# lmr33620.net
KiCad netlist of a schematic drawn in Altium Designer
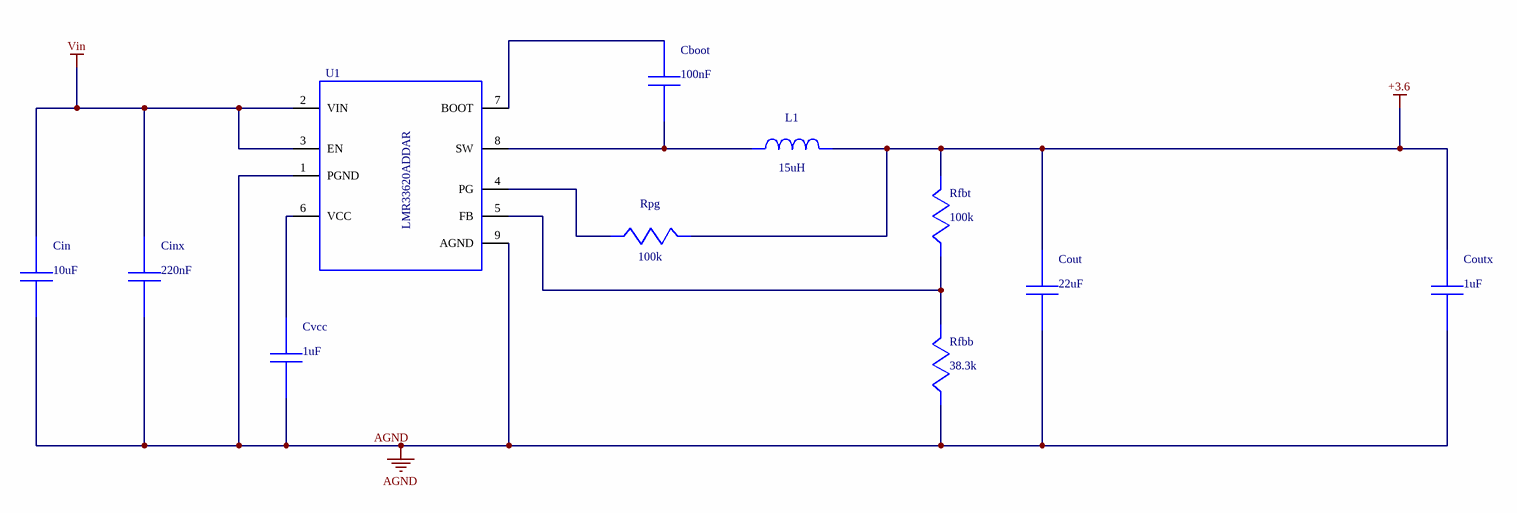
[diagram p0: lmr33620.schdoc]

(export (version "E")
  (design (tool "Eeschema 10.0.6"))
  (components
    (comp (ref "Cboot")
      (value "100nF")
      (footprint "0805_C")
      (description "HMK212B7104KG-T")
      (libsource (lib "TI WEBENCH") (part "Cboot"))
    )
    (comp (ref "Cin")
      (value "10uF")
      (footprint "1206_C")
      (description "C3216X5R1H106K16")
      (fields (field (name "BOM_MANUFACTURER PART") "C3216X5R1H106K160AB"))
      (libsource (lib "TI WEBENCH") (part "Cin"))
    )
    (comp (ref "Cinx")
      (value "220nF")
      (footprint "1206_C")
      (description "C3216X7R2A224K11")
      (fields (field (name "BOM_MANUFACTURER PART") "C3216X7R2A224K115AA"))
      (libsource (lib "TI WEBENCH") (part "Cinx"))
    )
    (comp (ref "Cout")
      (value "22uF")
      (footprint "0603_C")
      (description "GRM188R60J226MEA")
      (fields (field (name "BOM_MANUFACTURER PART") "GRM188R60J226MEA0D"))
      (libsource (lib "TI WEBENCH") (part "Cout"))
    )
    (comp (ref "Coutx")
      (value "1uF")
      (footprint "0805_C")
      (description "GRM21BR71A105KA0")
      (fields (field (name "BOM_MANUFACTURER PART") "GRM21BR71A105KA01L"))
      (libsource (lib "TI WEBENCH") (part "Coutx"))
    )
    (comp (ref "Cvcc")
      (value "1uF")
      (footprint "0603_C")
      (description "EMK107B7105KA-T")
      (libsource (lib "TI WEBENCH") (part "Cvcc"))
    )
    (comp (ref "L1")
      (value "15uH")
      (footprint "CDRH127")
      (description "CDRH127/LDNP-150")
      (fields (field (name "BOM_MANUFACTURER PART") "CDRH127/LDNP-150MC"))
      (libsource (lib "TI WEBENCH") (part "L1"))
    )
    (comp (ref "Rfbb")
      (value "38.3k")
      (footprint "0603_R")
      (description "CRCW060338K3FKEA")
      (libsource (lib "TI WEBENCH") (part "Rfbb"))
    )
    (comp (ref "Rfbt")
      (value "100k")
      (footprint "0805_R")
      (description "ERJ-6ENF1003V")
      (libsource (lib "TI WEBENCH") (part "Rfbt"))
    )
    (comp (ref "Rpg")
      (value "100k")
      (footprint "0603_R")
      (description "CRCW0603100KFKEA")
      (libsource (lib "TI WEBENCH") (part "Rpg"))
    )
    (comp (ref "U1")
      (value "LMR33620ADDAR")
      (footprint "DDA0008J")
      (libsource (lib "TI WEBENCH") (part "U1"))
    )
  )
  (nets
    (net (code "1") (name "+3.6") (class "Default")
      (node (ref "Cout") (pin "1") (pinfunction "1_1") (pintype "passive"))
      (node (ref "Coutx") (pin "1") (pinfunction "1_1") (pintype "passive"))
      (node (ref "L1") (pin "2") (pinfunction "2_2") (pintype "passive"))
      (node (ref "Rfbt") (pin "1") (pinfunction "1_1") (pintype "passive"))
      (node (ref "Rpg") (pin "1") (pinfunction "1_1") (pintype "passive"))
    )
    (net (code "2") (name "AGND") (class "Default")
      (node (ref "Cin") (pin "2") (pinfunction "2_2") (pintype "passive"))
      (node (ref "Cinx") (pin "2") (pinfunction "2_2") (pintype "passive"))
      (node (ref "Cout") (pin "2") (pinfunction "2_2") (pintype "passive"))
      (node (ref "Coutx") (pin "2") (pinfunction "2_2") (pintype "passive"))
      (node (ref "Cvcc") (pin "2") (pinfunction "2_2") (pintype "passive"))
      (node (ref "Rfbb") (pin "2") (pinfunction "2_2") (pintype "passive"))
      (node (ref "U1") (pin "1") (pinfunction "PGND_1") (pintype "passive"))
      (node (ref "U1") (pin "9") (pinfunction "AGND_9") (pintype "passive"))
    )
    (net (code "3") (name "Net-(U1-BOOT)") (class "Default")
      (node (ref "Cboot") (pin "1") (pinfunction "1_1") (pintype "passive"))
      (node (ref "U1") (pin "7") (pinfunction "BOOT_7") (pintype "passive"))
    )
    (net (code "4") (name "Net-(U1-FB)") (class "Default")
      (node (ref "Rfbb") (pin "1") (pinfunction "1_1") (pintype "passive"))
      (node (ref "Rfbt") (pin "2") (pinfunction "2_2") (pintype "passive"))
      (node (ref "U1") (pin "5") (pinfunction "FB_5") (pintype "passive"))
    )
    (net (code "5") (name "Net-(U1-PG)") (class "Default")
      (node (ref "Rpg") (pin "2") (pinfunction "2_2") (pintype "passive"))
      (node (ref "U1") (pin "4") (pinfunction "PG_4") (pintype "passive"))
    )
    (net (code "6") (name "Net-(U1-SW)") (class "Default")
      (node (ref "Cboot") (pin "2") (pinfunction "2_2") (pintype "passive"))
      (node (ref "L1") (pin "1") (pinfunction "1_1") (pintype "passive"))
      (node (ref "U1") (pin "8") (pinfunction "SW_8") (pintype "passive"))
    )
    (net (code "7") (name "Net-(U1-VCC)") (class "Default")
      (node (ref "Cvcc") (pin "1") (pinfunction "1_1") (pintype "passive"))
      (node (ref "U1") (pin "6") (pinfunction "VCC_6") (pintype "passive"))
    )
    (net (code "8") (name "Vin") (class "Default")
      (node (ref "Cin") (pin "1") (pinfunction "1_1") (pintype "passive"))
      (node (ref "Cinx") (pin "1") (pinfunction "1_1") (pintype "passive"))
      (node (ref "U1") (pin "2") (pinfunction "VIN_2") (pintype "passive"))
      (node (ref "U1") (pin "3") (pinfunction "EN_3") (pintype "passive"))
    )
  )
)
